# 05_-_MINIPCICONN.net
KiCad netlist of a schematic drawn in Altium Designer
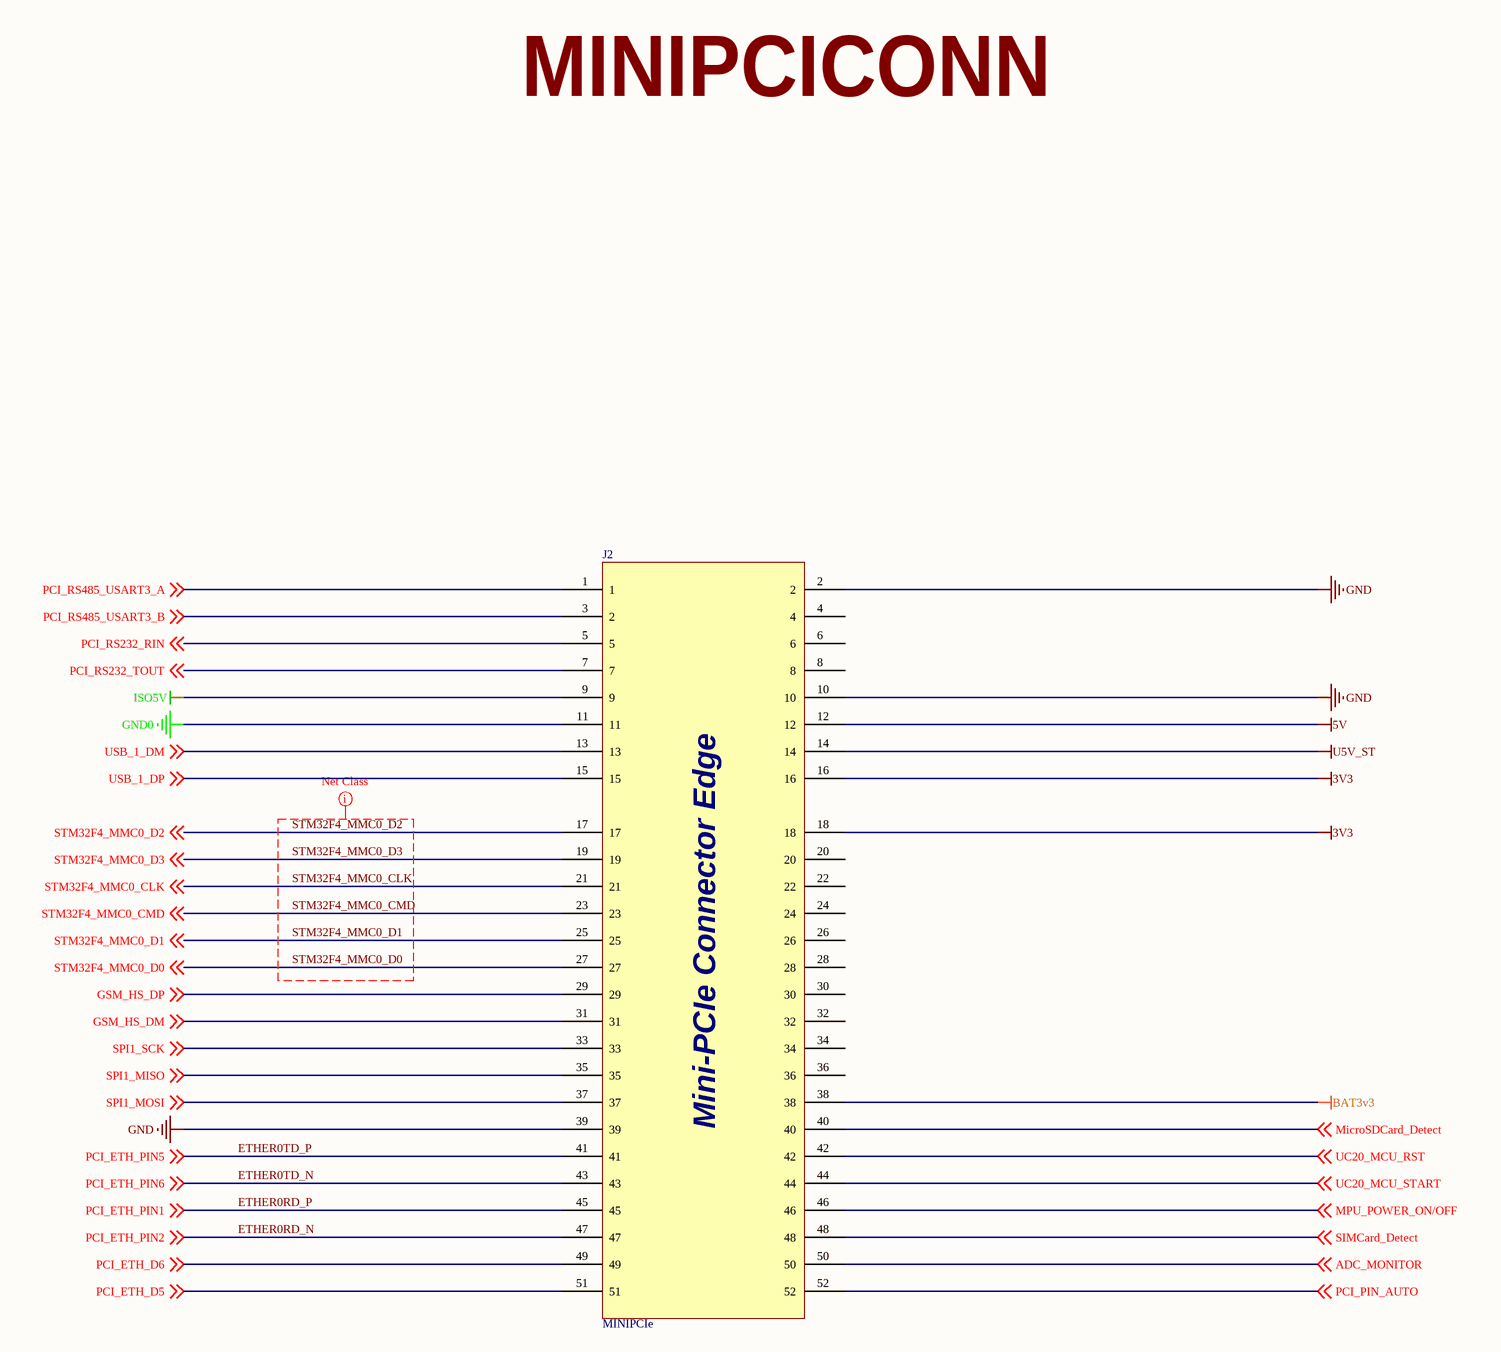
[diagram p0: [05] - MINIPCICONN.SchDoc]

(export (version "E")
  (design (tool "Eeschema 10.0.6"))
  (components
    (comp (ref "J2")
      (value "MINIPCIe")
      (footprint "MINI PCIe")
      (libsource (lib "CPU_STM_080816") (part "MINIPCIe"))
    )
  )
  (nets
    (net (code "1") (name "3V3") (class "Default")
      (node (ref "J2") (pin "16") (pinfunction "16_16") (pintype "passive"))
      (node (ref "J2") (pin "18") (pinfunction "18_18") (pintype "passive"))
    )
    (net (code "2") (name "5V") (class "Default")
      (node (ref "J2") (pin "12") (pinfunction "12_12") (pintype "passive"))
    )
    (net (code "3") (name "ADC_MONITOR") (class "Default")
      (node (ref "J2") (pin "50") (pinfunction "50_50") (pintype "passive"))
    )
    (net (code "4") (name "BAT3v3") (class "Default")
      (node (ref "J2") (pin "38") (pinfunction "38_38") (pintype "passive"))
    )
    (net (code "5") (name "GND") (class "Default")
      (node (ref "J2") (pin "10") (pinfunction "10_10") (pintype "passive"))
      (node (ref "J2") (pin "2") (pinfunction "2_2") (pintype "passive"))
      (node (ref "J2") (pin "39") (pinfunction "39_39") (pintype "passive"))
    )
    (net (code "6") (name "GND0") (class "Default")
      (node (ref "J2") (pin "11") (pinfunction "11_11") (pintype "passive"))
    )
    (net (code "7") (name "GSM_HS_DM") (class "Default")
      (node (ref "J2") (pin "31") (pinfunction "31_31") (pintype "passive"))
    )
    (net (code "8") (name "GSM_HS_DP") (class "Default")
      (node (ref "J2") (pin "29") (pinfunction "29_29") (pintype "passive"))
    )
    (net (code "9") (name "ISO5V") (class "Default")
      (node (ref "J2") (pin "9") (pinfunction "9_9") (pintype "passive"))
    )
    (net (code "10") (name "MPU_POWER_ON{slash}OFF") (class "Default")
      (node (ref "J2") (pin "46") (pinfunction "46_46") (pintype "passive"))
    )
    (net (code "11") (name "MicroSDCard_Detect") (class "Default")
      (node (ref "J2") (pin "40") (pinfunction "40_40") (pintype "passive"))
    )
    (net (code "12") (name "PCI_ETH_D5") (class "Default")
      (node (ref "J2") (pin "51") (pinfunction "51_51") (pintype "passive"))
    )
    (net (code "13") (name "PCI_ETH_D6") (class "Default")
      (node (ref "J2") (pin "49") (pinfunction "49_49") (pintype "passive"))
    )
    (net (code "14") (name "PCI_ETH_PIN1") (class "Default")
      (node (ref "J2") (pin "45") (pinfunction "45_45") (pintype "passive"))
    )
    (net (code "15") (name "PCI_ETH_PIN2") (class "Default")
      (node (ref "J2") (pin "47") (pinfunction "47_47") (pintype "passive"))
    )
    (net (code "16") (name "PCI_ETH_PIN5") (class "Default")
      (node (ref "J2") (pin "41") (pinfunction "41_41") (pintype "passive"))
    )
    (net (code "17") (name "PCI_ETH_PIN6") (class "Default")
      (node (ref "J2") (pin "43") (pinfunction "43_43") (pintype "passive"))
    )
    (net (code "18") (name "PCI_PIN_AUTO") (class "Default")
      (node (ref "J2") (pin "52") (pinfunction "52_52") (pintype "passive"))
    )
    (net (code "19") (name "PCI_RS232_RIN") (class "Default")
      (node (ref "J2") (pin "5") (pinfunction "5_5") (pintype "passive"))
    )
    (net (code "20") (name "PCI_RS232_TOUT") (class "Default")
      (node (ref "J2") (pin "7") (pinfunction "7_7") (pintype "passive"))
    )
    (net (code "21") (name "PCI_RS485_USART3_A") (class "Default")
      (node (ref "J2") (pin "1") (pinfunction "1_1") (pintype "passive"))
    )
    (net (code "22") (name "PCI_RS485_USART3_B") (class "Default")
      (node (ref "J2") (pin "3") (pinfunction "2_3") (pintype "passive"))
    )
    (net (code "23") (name "SIMCard_Detect") (class "Default")
      (node (ref "J2") (pin "48") (pinfunction "48_48") (pintype "passive"))
    )
    (net (code "24") (name "SPI1_MISO") (class "Default")
      (node (ref "J2") (pin "35") (pinfunction "35_35") (pintype "passive"))
    )
    (net (code "25") (name "SPI1_MOSI") (class "Default")
      (node (ref "J2") (pin "37") (pinfunction "37_37") (pintype "passive"))
    )
    (net (code "26") (name "SPI1_SCK") (class "Default")
      (node (ref "J2") (pin "33") (pinfunction "33_33") (pintype "passive"))
    )
    (net (code "27") (name "STM32F4_MMC0_CLK") (class "Default")
      (node (ref "J2") (pin "21") (pinfunction "21_21") (pintype "passive"))
    )
    (net (code "28") (name "STM32F4_MMC0_CMD") (class "Default")
      (node (ref "J2") (pin "23") (pinfunction "23_23") (pintype "passive"))
    )
    (net (code "29") (name "STM32F4_MMC0_D0") (class "Default")
      (node (ref "J2") (pin "27") (pinfunction "27_27") (pintype "passive"))
    )
    (net (code "30") (name "STM32F4_MMC0_D1") (class "Default")
      (node (ref "J2") (pin "25") (pinfunction "25_25") (pintype "passive"))
    )
    (net (code "31") (name "STM32F4_MMC0_D2") (class "Default")
      (node (ref "J2") (pin "17") (pinfunction "17_17") (pintype "passive"))
    )
    (net (code "32") (name "STM32F4_MMC0_D3") (class "Default")
      (node (ref "J2") (pin "19") (pinfunction "19_19") (pintype "passive"))
    )
    (net (code "33") (name "U5V_ST") (class "Default")
      (node (ref "J2") (pin "14") (pinfunction "14_14") (pintype "passive"))
    )
    (net (code "34") (name "UC20_MCU_RST") (class "Default")
      (node (ref "J2") (pin "42") (pinfunction "42_42") (pintype "passive"))
    )
    (net (code "35") (name "UC20_MCU_START") (class "Default")
      (node (ref "J2") (pin "44") (pinfunction "44_44") (pintype "passive"))
    )
    (net (code "36") (name "USB_1_DM") (class "Default")
      (node (ref "J2") (pin "13") (pinfunction "13_13") (pintype "passive"))
    )
    (net (code "37") (name "USB_1_DP") (class "Default")
      (node (ref "J2") (pin "15") (pinfunction "15_15") (pintype "passive"))
    )
    (net (code "38") (name "unconnected-(J2-Pad4)") (class "Default")
      (node (ref "J2") (pin "4") (pinfunction "4_4") (pintype "passive"))
    )
    (net (code "39") (name "unconnected-(J2-Pad6)") (class "Default")
      (node (ref "J2") (pin "6") (pinfunction "6_6") (pintype "passive"))
    )
    (net (code "40") (name "unconnected-(J2-Pad8)") (class "Default")
      (node (ref "J2") (pin "8") (pinfunction "8_8") (pintype "passive"))
    )
    (net (code "41") (name "unconnected-(J2-Pad20)") (class "Default")
      (node (ref "J2") (pin "20") (pinfunction "20_20") (pintype "passive"))
    )
    (net (code "42") (name "unconnected-(J2-Pad22)") (class "Default")
      (node (ref "J2") (pin "22") (pinfunction "22_22") (pintype "passive"))
    )
    (net (code "43") (name "unconnected-(J2-Pad24)") (class "Default")
      (node (ref "J2") (pin "24") (pinfunction "24_24") (pintype "passive"))
    )
    (net (code "44") (name "unconnected-(J2-Pad26)") (class "Default")
      (node (ref "J2") (pin "26") (pinfunction "26_26") (pintype "passive"))
    )
    (net (code "45") (name "unconnected-(J2-Pad28)") (class "Default")
      (node (ref "J2") (pin "28") (pinfunction "28_28") (pintype "passive"))
    )
    (net (code "46") (name "unconnected-(J2-Pad30)") (class "Default")
      (node (ref "J2") (pin "30") (pinfunction "30_30") (pintype "passive"))
    )
    (net (code "47") (name "unconnected-(J2-Pad32)") (class "Default")
      (node (ref "J2") (pin "32") (pinfunction "32_32") (pintype "passive"))
    )
    (net (code "48") (name "unconnected-(J2-Pad34)") (class "Default")
      (node (ref "J2") (pin "34") (pinfunction "34_34") (pintype "passive"))
    )
    (net (code "49") (name "unconnected-(J2-Pad36)") (class "Default")
      (node (ref "J2") (pin "36") (pinfunction "36_36") (pintype "passive"))
    )
  )
)
